# concentrador.net
KiCad netlist of a schematic drawn in Altium Designer
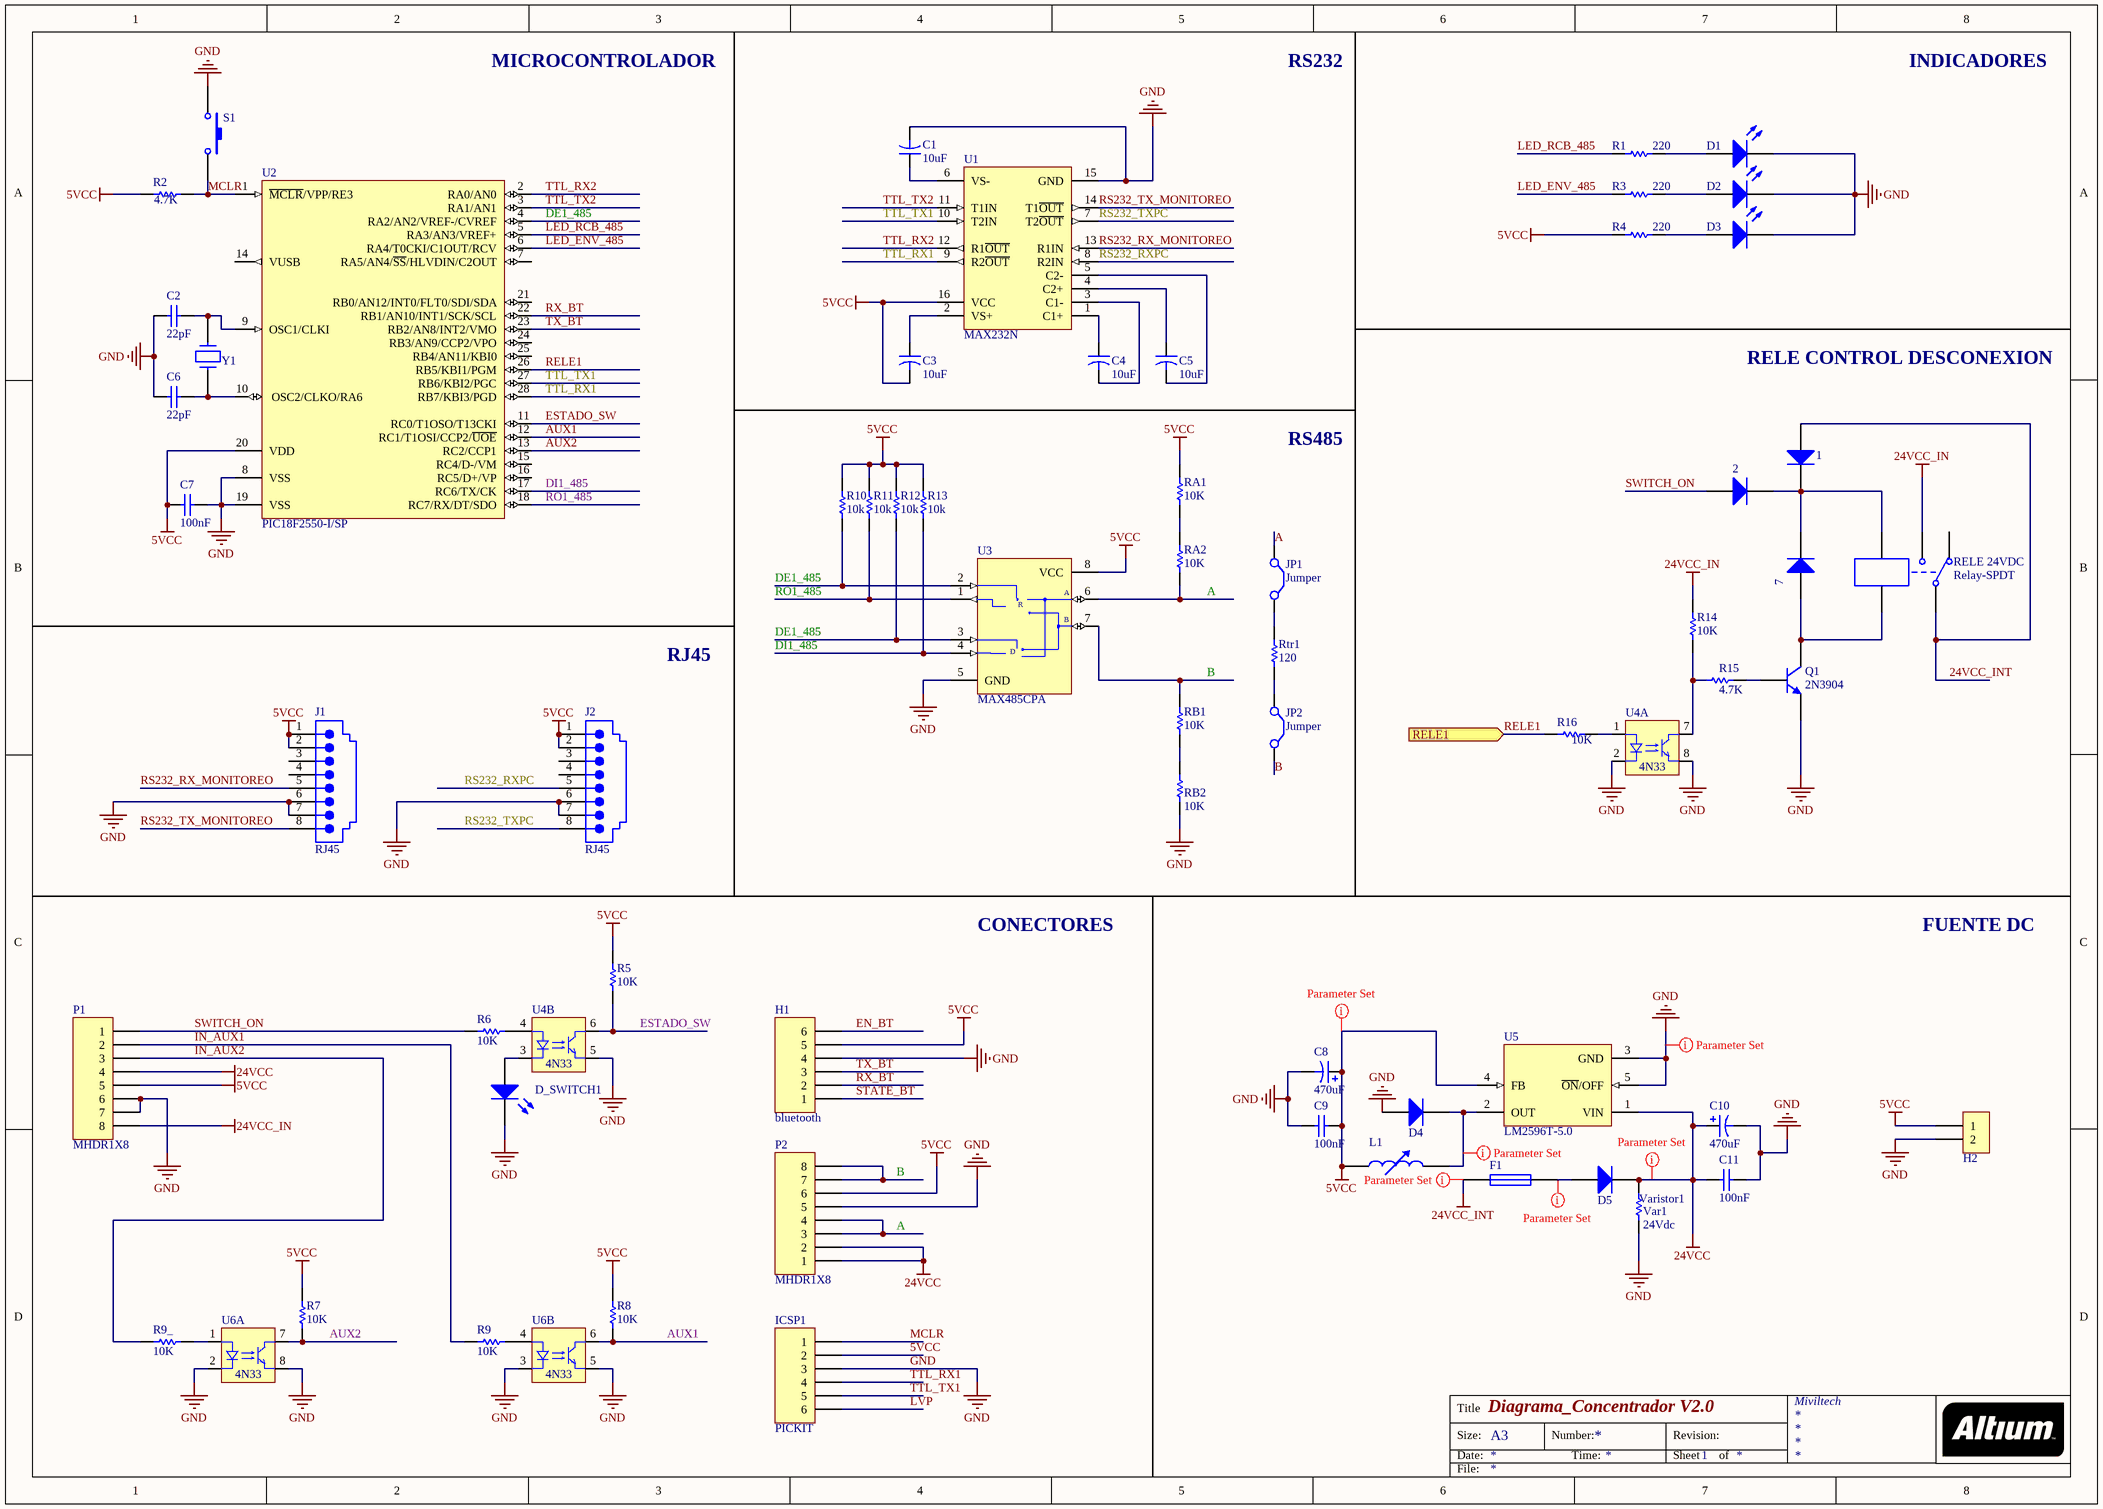
[diagram p0: concentrador.SchDoc]

(export (version "E")
  (design (tool "Eeschema 10.0.6"))
  (components
    (comp (ref "1")
      (value "Diode 1N4001")
      (footprint "DIODE-0.3A")
      (description "1 Amp General Purpose Rectifier")
      (fields (field (name "PUBLISHER") "Altium Limited"))
      (libsource (lib "Miscellaneous Devices") (part "Diode 1N4001"))
    )
    (comp (ref "2")
      (value "Diode 1N4001")
      (footprint "DIODE-0.3A")
      (description "1 Amp General Purpose Rectifier")
      (fields (field (name "PUBLISHER") "Altium Limited"))
      (libsource (lib "Miscellaneous Devices") (part "Diode 1N4001"))
    )
    (comp (ref "7")
      (value "Diode 1N4001")
      (footprint "DIODE-0.3A")
      (description "1 Amp General Purpose Rectifier")
      (fields (field (name "PUBLISHER") "Altium Limited"))
      (libsource (lib "Miscellaneous Devices") (part "Diode 1N4001"))
    )
    (comp (ref "C1")
      (value "10uF")
      (footprint "C1UF")
      (description "Capacitor")
      (fields (field (name "Comment") "Cap2") (field (name "PUBLISHER") "Altium Limited"))
      (libsource (lib "Miscellaneous Devices") (part "Cap2"))
    )
    (comp (ref "C2")
      (value "22pF")
      (footprint "VP31-2.5")
      (description "Dipped Radial Multilayer Ceramic Capacitor COG (NPO): 22pF, 100V")
      (fields (field (name "Comment") "VP31BA220JB") (field (name "PUBLISHER") "Altium Limited"))
      (libsource (lib "Vishay Vitramon Ceramic Dipped Capacitor") (part "VP31BA220JB"))
    )
    (comp (ref "C3")
      (value "10uF")
      (footprint "C1UF")
      (description "Capacitor")
      (fields (field (name "Comment") "Cap2") (field (name "PUBLISHER") "Altium Limited"))
      (libsource (lib "Miscellaneous Devices") (part "Cap2"))
    )
    (comp (ref "C4")
      (value "10uF")
      (footprint "C1UF")
      (description "Capacitor")
      (fields (field (name "Comment") "Cap2") (field (name "PUBLISHER") "Altium Limited"))
      (libsource (lib "Miscellaneous Devices") (part "Cap2"))
    )
    (comp (ref "C5")
      (value "10uF")
      (footprint "C1UF")
      (description "Capacitor")
      (fields (field (name "Comment") "Cap2") (field (name "PUBLISHER") "Altium Limited"))
      (libsource (lib "Miscellaneous Devices") (part "Cap2"))
    )
    (comp (ref "C6")
      (value "22pF")
      (footprint "VP31-2.5")
      (description "Dipped Radial Multilayer Ceramic Capacitor COG (NPO): 22pF, 100V")
      (fields (field (name "Comment") "VP31BA220JB") (field (name "PUBLISHER") "Altium Limited"))
      (libsource (lib "Vishay Vitramon Ceramic Dipped Capacitor") (part "VP31BA220JB"))
    )
    (comp (ref "C7")
      (value "100nF")
      (footprint "VP44-2.5")
      (description "Dipped Radial Multilayer Ceramic Capacitor X7R: 220nF, 100V")
      (fields (field (name "Comment") "VP44BY224JB") (field (name "PUBLISHER") "Altium Limited"))
      (libsource (lib "Vishay Vitramon Ceramic Dipped Capacitor") (part "VP44BY224JB"))
    )
    (comp (ref "C8")
      (value "470uF")
      (footprint "C1000UF")
      (description "Polarized Capacitor (Radial)")
      (fields (field (name "Comment") "Cap Pol1") (field (name "PUBLISHER") "Altium Limited"))
      (libsource (lib "Miscellaneous Devices") (part "Cap Pol1"))
    )
    (comp (ref "C9")
      (value "100nF")
      (footprint "VP44-2.5")
      (description "Dipped Radial Multilayer Ceramic Capacitor X7R: 220nF, 100V")
      (fields (field (name "Comment") "VP44BY224JB") (field (name "PUBLISHER") "Altium Limited"))
      (libsource (lib "Vishay Vitramon Ceramic Dipped Capacitor") (part "VP44BY224JB"))
    )
    (comp (ref "C10")
      (value "470uF")
      (footprint "C1000UF")
      (description "Polarized Capacitor (Radial)")
      (fields (field (name "Comment") "Cap Pol1") (field (name "PUBLISHER") "Altium Limited"))
      (libsource (lib "Miscellaneous Devices") (part "Cap Pol1"))
    )
    (comp (ref "C11")
      (value "100nF")
      (footprint "VP44-2.5")
      (description "Dipped Radial Multilayer Ceramic Capacitor X7R: 220nF, 100V")
      (fields (field (name "Comment") "VP44BY224JB") (field (name "PUBLISHER") "Altium Limited"))
      (libsource (lib "Vishay Vitramon Ceramic Dipped Capacitor") (part "VP44BY224JB"))
    )
    (comp (ref "D1")
      (value "LED0")
      (footprint "LED3MM green")
      (description "Typical INFRARED GaAs LED")
      (fields (field (name "PUBLISHER") "Altium Limited"))
      (libsource (lib "Miscellaneous Devices") (part "LED0"))
    )
    (comp (ref "D2")
      (value "LED0")
      (footprint "LED3MM green")
      (description "Typical INFRARED GaAs LED")
      (fields (field (name "PUBLISHER") "Altium Limited"))
      (libsource (lib "Miscellaneous Devices") (part "LED0"))
    )
    (comp (ref "D3")
      (value "LED0")
      (footprint "LED3MM green")
      (description "Typical INFRARED GaAs LED")
      (fields (field (name "PUBLISHER") "Altium Limited"))
      (libsource (lib "Miscellaneous Devices") (part "LED0"))
    )
    (comp (ref "D4")
      (value "Diodo")
      (footprint "1N4000")
      (description "Diodo rectificador")
      (libsource (lib "Diodos") (part "Diodo"))
    )
    (comp (ref "D5")
      (value "Diodo")
      (footprint "1N4000")
      (description "Diodo rectificador")
      (libsource (lib "Diodos") (part "Diodo"))
    )
    (comp (ref "D_SWITCH1")
      (value "LED0")
      (footprint "LED3MM green")
      (description "Typical INFRARED GaAs LED")
      (fields (field (name "PUBLISHER") "Altium Limited"))
      (libsource (lib "Miscellaneous Devices") (part "LED0"))
    )
    (comp (ref "F1")
      (value "Fuse")
      (footprint "PORTA_FUSE")
      (fields (field (name "PUBLISHER") "Altium Limited"))
      (libsource (lib "Miscellaneous Devices") (part "Fuse 1"))
    )
    (comp (ref "H1")
      (value "bluetooth")
      (footprint "Header 1X6")
      (description "Header, 6-Pin")
      (fields (field (name "PUBLISHER") "Altium Limited"))
      (libsource (lib "Conectores") (part "Header 6"))
    )
    (comp (ref "H2")
      (value "Header")
      (footprint "Header 1X2")
      (description "Header 2 pin")
      (libsource (lib "Conectores") (part "Header 2"))
    )
    (comp (ref "ICSP1")
      (value "PICKIT")
      (footprint "HDR1X6")
      (description "Header, 6-Pin")
      (fields (field (name "PUBLISHER") "Altium Limited"))
      (libsource (lib "CONTROL BARRAS DE CONTEO") (part "Header 6"))
    )
    (comp (ref "J1")
      (value "RJ45")
      (footprint "15-43-6233")
      (description "Right Angle, Standard Profile, RJ45-Keyed, Flange Mount PCB Jack")
      (fields (field (name "PUBLISHER") "Altium Limited"))
      (libsource (lib "Molex Modular Jack Right Angle") (part "15-43-6233"))
    )
    (comp (ref "J2")
      (value "RJ45")
      (footprint "15-43-6233")
      (description "Right Angle, Standard Profile, RJ45-Keyed, Flange Mount PCB Jack")
      (fields (field (name "PUBLISHER") "Altium Limited"))
      (libsource (lib "Molex Modular Jack Right Angle") (part "15-43-6233"))
    )
    (comp (ref "JP1")
      (value "Jumper")
      (footprint "RAD-0.2")
      (description "Jumper Wire")
      (fields (field (name "PUBLISHER") "Altium Limited"))
      (libsource (lib "Miscellaneous Devices") (part "Jumper"))
    )
    (comp (ref "JP2")
      (value "Jumper")
      (footprint "RAD-0.2")
      (description "Jumper Wire")
      (fields (field (name "PUBLISHER") "Altium Limited"))
      (libsource (lib "Miscellaneous Devices") (part "Jumper"))
    )
    (comp (ref "L1")
      (value "Inductor Adj")
      (footprint "Inductor_redondo")
      (description "Adjustable Inductor")
      (fields (field (name "PUBLISHER") "Altium Limited"))
      (libsource (lib "Miscellaneous Devices") (part "Inductor Adj"))
    )
    (comp (ref "P1")
      (value "MHDR1X8")
      (footprint "8PEQ_TAIYUE_OK")
      (description "Header, 8-Pin")
      (fields (field (name "PUBLISHER") "Altium Limited"))
      (libsource (lib "Miscellaneous Connectors") (part "MHDR1X8"))
    )
    (comp (ref "P2")
      (value "MHDR1X8")
      (footprint "8PEQ_TAIYUE_OK")
      (description "Header, 8-Pin")
      (fields (field (name "PUBLISHER") "Altium Limited"))
      (libsource (lib "") (part "MHDR1X8_1"))
    )
    (comp (ref "Q1")
      (value "2N3904")
      (footprint "2N3904_OK")
      (description "NPN General Purpose Amplifier")
      (fields (field (name "PUBLISHER") "Altium Limited"))
      (libsource (lib "Miscellaneous Devices") (part "2N3904"))
    )
    (comp (ref "R1")
      (value "220")
      (footprint "AXIAL-0.3")
      (description "Resistor")
      (fields (field (name "Comment") "Res1") (field (name "PUBLISHER") "Altium Limited"))
      (libsource (lib "Miscellaneous Devices") (part "Res1"))
    )
    (comp (ref "R2")
      (value "4.7K")
      (footprint "AXIAL-0.3")
      (description "Resistor")
      (fields (field (name "Comment") "Res1") (field (name "PUBLISHER") "Altium Limited"))
      (libsource (lib "Miscellaneous Devices") (part "Res1"))
    )
    (comp (ref "R3")
      (value "220")
      (footprint "AXIAL-0.3")
      (description "Resistor")
      (fields (field (name "Comment") "Res1") (field (name "PUBLISHER") "Altium Limited"))
      (libsource (lib "Miscellaneous Devices") (part "Res1"))
    )
    (comp (ref "R4")
      (value "220")
      (footprint "AXIAL-0.3")
      (description "Resistor")
      (fields (field (name "Comment") "Res1") (field (name "PUBLISHER") "Altium Limited"))
      (libsource (lib "Miscellaneous Devices") (part "Res1"))
    )
    (comp (ref "R5")
      (value "10K")
      (footprint "AXIAL-0.3")
      (description "Resistor")
      (fields (field (name "Comment") "Res1") (field (name "PUBLISHER") "Altium Limited"))
      (libsource (lib "Miscellaneous Devices") (part "Res1"))
    )
    (comp (ref "R6")
      (value "10K")
      (footprint "AXIAL-0.3")
      (description "Resistor")
      (fields (field (name "Comment") "Res1") (field (name "PUBLISHER") "Altium Limited"))
      (libsource (lib "Miscellaneous Devices") (part "Res1"))
    )
    (comp (ref "R7")
      (value "10K")
      (footprint "AXIAL-0.3")
      (description "Resistor")
      (fields (field (name "Comment") "Res1") (field (name "PUBLISHER") "Altium Limited"))
      (libsource (lib "Miscellaneous Devices") (part "Res1"))
    )
    (comp (ref "R8")
      (value "10K")
      (footprint "AXIAL-0.3")
      (description "Resistor")
      (fields (field (name "Comment") "Res1") (field (name "PUBLISHER") "Altium Limited"))
      (libsource (lib "Miscellaneous Devices") (part "Res1"))
    )
    (comp (ref "R9")
      (value "10K")
      (footprint "AXIAL-0.3")
      (description "Resistor")
      (fields (field (name "Comment") "Res1") (field (name "PUBLISHER") "Altium Limited"))
      (libsource (lib "Miscellaneous Devices") (part "Res1"))
    )
    (comp (ref "R9_")
      (value "10K")
      (footprint "AXIAL-0.3")
      (description "Resistor")
      (fields (field (name "Comment") "Res1") (field (name "PUBLISHER") "Altium Limited"))
      (libsource (lib "Miscellaneous Devices") (part "Res1"))
    )
    (comp (ref "R10")
      (value "10k")
      (footprint "AXIAL-0.3")
      (description "Resistor")
      (fields (field (name "Comment") "Res1") (field (name "PUBLISHER") "Altium Limited"))
      (libsource (lib "Miscellaneous Devices") (part "Res1"))
    )
    (comp (ref "R11")
      (value "10k")
      (footprint "AXIAL-0.3")
      (description "Resistor")
      (fields (field (name "Comment") "Res1") (field (name "PUBLISHER") "Altium Limited"))
      (libsource (lib "Miscellaneous Devices") (part "Res1"))
    )
    (comp (ref "R12")
      (value "10k")
      (footprint "AXIAL-0.3")
      (description "Resistor")
      (fields (field (name "Comment") "Res1") (field (name "PUBLISHER") "Altium Limited"))
      (libsource (lib "Miscellaneous Devices") (part "Res1"))
    )
    (comp (ref "R13")
      (value "10k")
      (footprint "AXIAL-0.3")
      (description "Resistor")
      (fields (field (name "Comment") "Res1") (field (name "PUBLISHER") "Altium Limited"))
      (libsource (lib "Miscellaneous Devices") (part "Res1"))
    )
    (comp (ref "R14")
      (value "10K")
      (footprint "AXIAL-0.3")
      (description "Resistor")
      (fields (field (name "Comment") "Res1") (field (name "PUBLISHER") "Altium Limited"))
      (libsource (lib "Miscellaneous Devices") (part "Res1"))
    )
    (comp (ref "R15")
      (value "4.7K")
      (footprint "AXIAL-0.3")
      (description "Resistor")
      (fields (field (name "Comment") "Res1") (field (name "PUBLISHER") "Altium Limited"))
      (libsource (lib "Miscellaneous Devices") (part "Res1"))
    )
    (comp (ref "R16")
      (value "10K")
      (footprint "AXIAL-0.3")
      (description "Resistor")
      (fields (field (name "Comment") "Res1") (field (name "PUBLISHER") "Altium Limited"))
      (libsource (lib "Miscellaneous Devices") (part "Res1"))
    )
    (comp (ref "RA1")
      (value "10K")
      (footprint "AXIAL-0.3")
      (description "Resistor")
      (fields (field (name "Comment") "Res1") (field (name "PUBLISHER") "Altium Limited"))
      (libsource (lib "Miscellaneous Devices") (part "Res1"))
    )
    (comp (ref "RA2")
      (value "10K")
      (footprint "AXIAL-0.3")
      (description "Resistor")
      (fields (field (name "Comment") "Res1") (field (name "PUBLISHER") "Altium Limited"))
      (libsource (lib "Miscellaneous Devices") (part "Res1"))
    )
    (comp (ref "RB1")
      (value "10K")
      (footprint "AXIAL-0.3")
      (description "Resistor")
      (fields (field (name "Comment") "Res1") (field (name "PUBLISHER") "Altium Limited"))
      (libsource (lib "Miscellaneous Devices") (part "Res1"))
    )
    (comp (ref "RB2")
      (value "10K")
      (footprint "AXIAL-0.3")
      (description "Resistor")
      (fields (field (name "Comment") "Res1") (field (name "PUBLISHER") "Altium Limited"))
      (libsource (lib "Miscellaneous Devices") (part "Res1"))
    )
    (comp (ref "RELE 24VDC")
      (value "Relay-SPDT")
      (footprint "MODULE5B")
      (description "Single-Pole Dual-Throw Relay")
      (fields (field (name "PUBLISHER") "Altium Limited"))
      (libsource (lib "Miscellaneous Devices") (part "Relay-SPDT"))
    )
    (comp (ref "Rtr1")
      (value "120")
      (footprint "AXIAL-0.3")
      (description "Resistor")
      (fields (field (name "Comment") "Res1") (field (name "PUBLISHER") "Altium Limited"))
      (libsource (lib "Miscellaneous Devices") (part "Res1"))
    )
    (comp (ref "S1")
      (value "Push Button")
      (footprint "PULSA4")
      (description "Switch")
      (fields (field (name "PUBLISHER") "Altium Limited"))
      (libsource (lib "Botones") (part "Push Button"))
    )
    (comp (ref "U1")
      (value "MAX232N")
      (footprint "N016")
      (description "Dual EIA-232 Driver/Receiver")
      (fields (field (name "PUBLISHER") "Altium Limited"))
      (libsource (lib "TI Interface Line Transceiver") (part "MAX232N"))
    )
    (comp (ref "U2")
      (value "PIC18F2550-I/SP")
      (footprint "SPDIP300-SP28")
      (fields (field (name "PUBLISHER") "Altium Limited"))
      (libsource (lib "Microchip Microcontroller 8-Bit PIC18") (part "PIC18F2550-I/SP"))
    )
    (comp (ref "U3")
      (value "MAX485CPA")
      (footprint "PA8")
      (description "Low-Power, Slew-Rate-Limited RS-485/RS-422 Transceiver")
      (fields (field (name "PUBLISHER") "Altium Limited"))
      (libsource (lib "Maxim Communication Transceiver") (part "MAX485CPA"))
    )
    (comp (ref "U4")
      (value "4N33")
      (footprint "4n35_4n33_6pines")
      (description "Optocoupler, Phototransistor Output, Dual Channel, TTL Compatible, Pb-free")
      (fields (field (name "PUBLISHER") "Altium Limited"))
      (libsource (lib "Vishay Optoelectronic Optocoupler") (part "ILD74"))
    )
    (comp (ref "U5")
      (value "LM2596T-5.0")
      (footprint "FP_LM2596_D_PCB")
      (description "SIMPLE SWITCHER Power Converter 150 KHz 3A Step-Down Voltage Regulator")
      (fields
        (field (name "MANUFACTURER") "National Semiconductor")
        (field (name "DIGIKEYPARTNUMBER") "LM2596T-5.0-ND")
        (field (name "PUBLISHER") "Altium Limited")
      )
      (libsource (lib "NSC Switcher") (part "LM2596T-5.0"))
    )
    (comp (ref "U6")
      (value "4N33")
      (footprint "4n35_4n33_6pines")
      (description "Optocoupler, Phototransistor Output, Dual Channel, TTL Compatible, Pb-free")
      (fields (field (name "PUBLISHER") "Altium Limited"))
      (libsource (lib "Vishay Optoelectronic Optocoupler") (part "ILD74"))
    )
    (comp (ref "Varistor1")
      (value "Var1")
      (footprint "AXIAL-0.3")
      (description "Resistor")
      (fields (field (name "ALTIUM_VALUE") "24Vdc") (field (name "PUBLISHER") "Altium Limited"))
      (libsource (lib "Miscellaneous Devices") (part "Res1"))
    )
    (comp (ref "Y1")
      (value "XTAL")
      (footprint "Cristal mini")
      (description "Cristal de cuarzo")
      (libsource (lib "Cristales de cuarzo") (part "Cristal de cuarzo"))
    )
  )
  (nets
    (net (code "1") (name "/A") (class "Default")
      (node (ref "JP1") (pin "1") (pinfunction "C1_1") (pintype "passive"))
      (node (ref "P2") (pin "3") (pinfunction "3_3") (pintype "passive"))
      (node (ref "P2") (pin "4") (pinfunction "4_4") (pintype "passive"))
      (node (ref "RA2") (pin "1") (pinfunction "1_1") (pintype "passive"))
      (node (ref "U3") (pin "6") (pinfunction "A_6") (pintype "bidirectional"))
    )
    (net (code "2") (name "/AUX1") (class "Default")
      (node (ref "R8") (pin "2") (pinfunction "2_2") (pintype "passive"))
      (node (ref "U2") (pin "12") (pinfunction "RC1/T1OSI/CCP2/~{UOE}_12") (pintype "bidirectional"))
      (node (ref "U6") (pin "6") (pinfunction "C_6") (pintype "passive"))
    )
    (net (code "3") (name "/AUX2") (class "Default")
      (node (ref "R7") (pin "2") (pinfunction "2_2") (pintype "passive"))
      (node (ref "U2") (pin "13") (pinfunction "RC2/CCP1_13") (pintype "bidirectional"))
      (node (ref "U6") (pin "7") (pinfunction "C_7") (pintype "passive"))
    )
    (net (code "4") (name "/B") (class "Default")
      (node (ref "JP2") (pin "2") (pinfunction "C2_2") (pintype "passive"))
      (node (ref "P2") (pin "7") (pinfunction "7_7") (pintype "passive"))
      (node (ref "P2") (pin "8") (pinfunction "8_8") (pintype "passive"))
      (node (ref "RB1") (pin "1") (pinfunction "1_1") (pintype "passive"))
      (node (ref "U3") (pin "7") (pinfunction "B_7") (pintype "bidirectional"))
    )
    (net (code "5") (name "/DE1_485") (class "Default")
      (node (ref "R10") (pin "1") (pinfunction "1_1") (pintype "passive"))
      (node (ref "R12") (pin "1") (pinfunction "1_1") (pintype "passive"))
      (node (ref "U2") (pin "4") (pinfunction "RA2/AN2/VREF-/CVREF_4") (pintype "bidirectional"))
      (node (ref "U3") (pin "2") (pinfunction "~{RE}_2") (pintype "input"))
      (node (ref "U3") (pin "3") (pinfunction "DE_3") (pintype "input"))
    )
    (net (code "6") (name "/DI1_485") (class "Default")
      (node (ref "R13") (pin "1") (pinfunction "1_1") (pintype "passive"))
      (node (ref "U2") (pin "17") (pinfunction "RC6/TX/CK_17") (pintype "bidirectional"))
      (node (ref "U3") (pin "4") (pinfunction "DI_4") (pintype "input"))
    )
    (net (code "7") (name "/EN_BT") (class "Default")
      (node (ref "H1") (pin "6") (pinfunction "6_6") (pintype "passive"))
    )
    (net (code "8") (name "/ESTADO_SW") (class "Default")
      (node (ref "R5") (pin "2") (pinfunction "2_2") (pintype "passive"))
      (node (ref "U2") (pin "11") (pinfunction "RC0/T1OSO/T13CKI_11") (pintype "bidirectional"))
      (node (ref "U4") (pin "6") (pinfunction "C_6") (pintype "passive"))
    )
    (net (code "9") (name "/IN_AUX1") (class "Default")
      (node (ref "P1") (pin "2") (pinfunction "2_2") (pintype "passive"))
      (node (ref "R9") (pin "2") (pinfunction "2_2") (pintype "passive"))
    )
    (net (code "10") (name "/IN_AUX2") (class "Default")
      (node (ref "P1") (pin "3") (pinfunction "3_3") (pintype "passive"))
      (node (ref "R9_") (pin "2") (pinfunction "2_2") (pintype "passive"))
    )
    (net (code "11") (name "/LED_ENV_485") (class "Default")
      (node (ref "R3") (pin "1") (pinfunction "1_1") (pintype "passive"))
      (node (ref "U2") (pin "6") (pinfunction "RA4/T0CKI/C1OUT/RCV_6") (pintype "bidirectional"))
    )
    (net (code "12") (name "/LED_RCB_485") (class "Default")
      (node (ref "R1") (pin "1") (pinfunction "1_1") (pintype "passive"))
      (node (ref "U2") (pin "5") (pinfunction "RA3/AN3/VREF+_5") (pintype "bidirectional"))
    )
    (net (code "13") (name "/LVP") (class "Default")
      (node (ref "ICSP1") (pin "6") (pinfunction "6_6") (pintype "passive"))
    )
    (net (code "14") (name "/MCLR") (class "Default")
      (node (ref "ICSP1") (pin "1") (pinfunction "1_1") (pintype "passive"))
      (node (ref "R2") (pin "2") (pinfunction "2_2") (pintype "passive"))
      (node (ref "S1") (pin "2") (pinfunction "2_2") (pintype "passive"))
      (node (ref "U2") (pin "1") (pinfunction "~{MCLR}/VPP/RE3_1") (pintype "input"))
    )
    (net (code "15") (name "/RELE1") (class "Default")
      (node (ref "R16") (pin "2") (pinfunction "2_2") (pintype "passive"))
      (node (ref "U2") (pin "26") (pinfunction "RB5/KBI1/PGM_26") (pintype "bidirectional"))
    )
    (net (code "16") (name "/RO1_485") (class "Default")
      (node (ref "R11") (pin "1") (pinfunction "1_1") (pintype "passive"))
      (node (ref "U2") (pin "18") (pinfunction "RC7/RX/DT/SDO_18") (pintype "bidirectional"))
      (node (ref "U3") (pin "1") (pinfunction "RO_1") (pintype "output"))
    )
    (net (code "17") (name "/RS232_RXPC") (class "Default")
      (node (ref "J2") (pin "5") (pinfunction "5_5") (pintype "passive"))
      (node (ref "U1") (pin "8") (pinfunction "R2IN_8") (pintype "input"))
    )
    (net (code "18") (name "/RS232_RX_MONITOREO") (class "Default")
      (node (ref "J1") (pin "5") (pinfunction "5_5") (pintype "passive"))
      (node (ref "U1") (pin "13") (pinfunction "R1IN_13") (pintype "input"))
    )
    (net (code "19") (name "/RS232_TXPC") (class "Default")
      (node (ref "J2") (pin "8") (pinfunction "8_8") (pintype "passive"))
      (node (ref "U1") (pin "7") (pinfunction "T2~{OUT}_7") (pintype "output"))
    )
    (net (code "20") (name "/RS232_TX_MONITOREO") (class "Default")
      (node (ref "J1") (pin "8") (pinfunction "8_8") (pintype "passive"))
      (node (ref "U1") (pin "14") (pinfunction "T1~{OUT}_14") (pintype "output"))
    )
    (net (code "21") (name "/RX_BT") (class "Default")
      (node (ref "H1") (pin "2") (pinfunction "2_2") (pintype "passive"))
      (node (ref "U2") (pin "22") (pinfunction "RB1/AN10/INT1/SCK/SCL_22") (pintype "bidirectional"))
    )
    (net (code "22") (name "/STATE_BT") (class "Default")
      (node (ref "H1") (pin "1") (pinfunction "1_1") (pintype "passive"))
    )
    (net (code "23") (name "/SWITCH_ON") (class "Default")
      (node (ref "2") (pin "1") (pinfunction "A_1") (pintype "passive"))
      (node (ref "P1") (pin "1") (pinfunction "1_1") (pintype "passive"))
      (node (ref "R6") (pin "2") (pinfunction "2_2") (pintype "passive"))
    )
    (net (code "24") (name "/TTL_RX1") (class "Default")
      (node (ref "ICSP1") (pin "4") (pinfunction "4_4") (pintype "passive"))
      (node (ref "U1") (pin "9") (pinfunction "R2~{OUT}_9") (pintype "output"))
      (node (ref "U2") (pin "28") (pinfunction "RB7/KBI3/PGD_28") (pintype "bidirectional"))
    )
    (net (code "25") (name "/TTL_RX2") (class "Default")
      (node (ref "U1") (pin "12") (pinfunction "R1~{OUT}_12") (pintype "output"))
      (node (ref "U2") (pin "2") (pinfunction "RA0/AN0_2") (pintype "bidirectional"))
    )
    (net (code "26") (name "/TTL_TX1") (class "Default")
      (node (ref "ICSP1") (pin "5") (pinfunction "5_5") (pintype "passive"))
      (node (ref "U1") (pin "10") (pinfunction "T2IN_10") (pintype "input"))
      (node (ref "U2") (pin "27") (pinfunction "RB6/KBI2/PGC_27") (pintype "bidirectional"))
    )
    (net (code "27") (name "/TTL_TX2") (class "Default")
      (node (ref "U1") (pin "11") (pinfunction "T1IN_11") (pintype "input"))
      (node (ref "U2") (pin "3") (pinfunction "RA1/AN1_3") (pintype "bidirectional"))
    )
    (net (code "28") (name "/TX_BT") (class "Default")
      (node (ref "H1") (pin "3") (pinfunction "3_3") (pintype "passive"))
      (node (ref "U2") (pin "23") (pinfunction "RB2/AN8/INT2/VMO_23") (pintype "bidirectional"))
    )
    (net (code "29") (name "5VCC") (class "Default")
      (node (ref "C3") (pin "2") (pinfunction "2_2") (pintype "passive"))
      (node (ref "C7") (pin "1") (pinfunction "1_1") (pintype "passive"))
      (node (ref "C8") (pin "1") (pinfunction "1_1") (pintype "passive"))
      (node (ref "C9") (pin "2") (pinfunction "2_2") (pintype "passive"))
      (node (ref "H1") (pin "5") (pinfunction "5_5") (pintype "passive"))
      (node (ref "H2") (pin "1") (pinfunction "1_1") (pintype "passive"))
      (node (ref "ICSP1") (pin "2") (pinfunction "2_2") (pintype "passive"))
      (node (ref "J1") (pin "1") (pinfunction "1_1") (pintype "passive"))
      (node (ref "J1") (pin "2") (pinfunction "2_2") (pintype "passive"))
      (node (ref "J2") (pin "1") (pinfunction "1_1") (pintype "passive"))
      (node (ref "J2") (pin "2") (pinfunction "2_2") (pintype "passive"))
      (node (ref "L1") (pin "1") (pinfunction "1_1") (pintype "passive"))
      (node (ref "P1") (pin "5") (pinfunction "5_5") (pintype "passive"))
      (node (ref "P2") (pin "6") (pinfunction "6_6") (pintype "passive"))
      (node (ref "R10") (pin "2") (pinfunction "2_2") (pintype "passive"))
      (node (ref "R11") (pin "2") (pinfunction "2_2") (pintype "passive"))
      (node (ref "R12") (pin "2") (pinfunction "2_2") (pintype "passive"))
      (node (ref "R13") (pin "2") (pinfunction "2_2") (pintype "passive"))
      (node (ref "R2") (pin "1") (pinfunction "1_1") (pintype "passive"))
      (node (ref "R4") (pin "1") (pinfunction "1_1") (pintype "passive"))
      (node (ref "R5") (pin "1") (pinfunction "1_1") (pintype "passive"))
      (node (ref "R7") (pin "1") (pinfunction "1_1") (pintype "passive"))
      (node (ref "R8") (pin "1") (pinfunction "1_1") (pintype "passive"))
      (node (ref "RA1") (pin "1") (pinfunction "1_1") (pintype "passive"))
      (node (ref "U1") (pin "16") (pinfunction "VCC_16") (pintype "power_in"))
      (node (ref "U2") (pin "20") (pinfunction "VDD_20") (pintype "power_in"))
      (node (ref "U3") (pin "8") (pinfunction "VCC_8") (pintype "power_in"))
      (node (ref "U5") (pin "4") (pinfunction "FB_4") (pintype "input"))
    )
    (net (code "30") (name "24VCC") (class "Default")
      (node (ref "C10") (pin "1") (pinfunction "1_1") (pintype "passive"))
      (node (ref "C11") (pin "1") (pinfunction "1_1") (pintype "passive"))
      (node (ref "D5") (pin "2") (pinfunction "K_2") (pintype "passive"))
      (node (ref "P1") (pin "4") (pinfunction "4_4") (pintype "passive"))
      (node (ref "P2") (pin "1") (pinfunction "1_1") (pintype "passive"))
      (node (ref "P2") (pin "2") (pinfunction "2_2") (pintype "passive"))
      (node (ref "U5") (pin "1") (pinfunction "VIN_1") (pintype "power_in"))
      (node (ref "Varistor1") (pin "2") (pinfunction "2_2") (pintype "passive"))
    )
    (net (code "31") (name "24VCC_IN") (class "Default")
      (node (ref "P1") (pin "8") (pinfunction "8_8") (pintype "passive"))
      (node (ref "R14") (pin "1") (pinfunction "1_1") (pintype "passive"))
      (node (ref "RELE 24VDC") (pin "3") (pinfunction "3_3") (pintype "passive"))
    )
    (net (code "32") (name "24VCC_INT") (class "Default")
      (node (ref "1") (pin "1") (pinfunction "A_1") (pintype "passive"))
      (node (ref "F1") (pin "2") (pinfunction "2_2") (pintype "passive"))
      (node (ref "RELE 24VDC") (pin "1") (pinfunction "1_1") (pintype "passive"))
    )
    (net (code "33") (name "GND") (class "Default")
      (node (ref "C1") (pin "2") (pinfunction "2_2") (pintype "passive"))
      (node (ref "C10") (pin "2") (pinfunction "2_2") (pintype "passive"))
      (node (ref "C11") (pin "2") (pinfunction "2_2") (pintype "passive"))
      (node (ref "C2") (pin "2") (pinfunction "2_2") (pintype "passive"))
      (node (ref "C6") (pin "2") (pinfunction "2_2") (pintype "passive"))
      (node (ref "C7") (pin "2") (pinfunction "2_2") (pintype "passive"))
      (node (ref "C8") (pin "2") (pinfunction "2_2") (pintype "passive"))
      (node (ref "C9") (pin "1") (pinfunction "1_1") (pintype "passive"))
      (node (ref "D1") (pin "2") (pinfunction "K_2") (pintype "passive"))
      (node (ref "D2") (pin "2") (pinfunction "K_2") (pintype "passive"))
      (node (ref "D3") (pin "2") (pinfunction "K_2") (pintype "passive"))
      (node (ref "D4") (pin "1") (pinfunction "A_1") (pintype "passive"))
      (node (ref "D_SWITCH1") (pin "2") (pinfunction "K_2") (pintype "passive"))
      (node (ref "H1") (pin "4") (pinfunction "4_4") (pintype "passive"))
      (node (ref "H2") (pin "2") (pinfunction "2_2") (pintype "passive"))
      (node (ref "ICSP1") (pin "3") (pinfunction "3_3") (pintype "passive"))
      (node (ref "J1") (pin "6") (pinfunction "6_6") (pintype "passive"))
      (node (ref "J1") (pin "7") (pinfunction "7_7") (pintype "passive"))
      (node (ref "J2") (pin "6") (pinfunction "6_6") (pintype "passive"))
      (node (ref "J2") (pin "7") (pinfunction "7_7") (pintype "passive"))
      (node (ref "P1") (pin "6") (pinfunction "6_6") (pintype "passive"))
      (node (ref "P1") (pin "7") (pinfunction "7_7") (pintype "passive"))
      (node (ref "P2") (pin "5") (pinfunction "5_5") (pintype "passive"))
      (node (ref "Q1") (pin "1") (pinfunction "E_1") (pintype "passive"))
      (node (ref "RB2") (pin "1") (pinfunction "1_1") (pintype "passive"))
      (node (ref "S1") (pin "1") (pinfunction "1_1") (pintype "passive"))
      (node (ref "U1") (pin "15") (pinfunction "GND_15") (pintype "power_in"))
      (node (ref "U2") (pin "19") (pinfunction "VSS_19") (pintype "power_in"))
      (node (ref "U2") (pin "8") (pinfunction "VSS_8") (pintype "power_in"))
      (node (ref "U3") (pin "5") (pinfunction "GND_5") (pintype "power_in"))
      (node (ref "U4") (pin "2") (pinfunction "K_2") (pintype "passive"))
      (node (ref "U4") (pin "5") (pinfunction "E_5") (pintype "passive"))
      (node (ref "U4") (pin "8") (pinfunction "E_8") (pintype "passive"))
      (node (ref "U5") (pin "3") (pinfunction "GND_3") (pintype "power_in"))
      (node (ref "U5") (pin "5") (pinfunction "~{ON}/OFF_5") (pintype "input"))
      (node (ref "U6") (pin "2") (pinfunction "K_2") (pintype "passive"))
      (node (ref "U6") (pin "3") (pinfunction "K_3") (pintype "passive"))
      (node (ref "U6") (pin "5") (pinfunction "E_5") (pintype "passive"))
      (node (ref "U6") (pin "8") (pinfunction "E_8") (pintype "passive"))
      (node (ref "Varistor1") (pin "1") (pinfunction "1_1") (pintype "passive"))
    )
    (net (code "34") (name "Net-(1-K)") (class "Default")
      (node (ref "1") (pin "2") (pinfunction "K_2") (pintype "passive"))
      (node (ref "2") (pin "2") (pinfunction "K_2") (pintype "passive"))
      (node (ref "7") (pin "2") (pinfunction "K_2") (pintype "passive"))
      (node (ref "RELE 24VDC") (pin "5") (pinfunction "5_5") (pintype "passive"))
    )
    (net (code "35") (name "Net-(7-A)") (class "Default")
      (node (ref "7") (pin "1") (pinfunction "A_1") (pintype "passive"))
      (node (ref "Q1") (pin "3") (pinfunction "C_3") (pintype "passive"))
      (node (ref "RELE 24VDC") (pin "4") (pinfunction "4_4") (pintype "passive"))
    )
    (net (code "36") (name "Net-(D1-A)") (class "Default")
      (node (ref "D1") (pin "1") (pinfunction "A_1") (pintype "passive"))
      (node (ref "R1") (pin "2") (pinfunction "2_2") (pintype "passive"))
    )
    (net (code "37") (name "Net-(D2-A)") (class "Default")
      (node (ref "D2") (pin "1") (pinfunction "A_1") (pintype "passive"))
      (node (ref "R3") (pin "2") (pinfunction "2_2") (pintype "passive"))
    )
    (net (code "38") (name "Net-(D3-A)") (class "Default")
      (node (ref "D3") (pin "1") (pinfunction "A_1") (pintype "passive"))
      (node (ref "R4") (pin "2") (pinfunction "2_2") (pintype "passive"))
    )
    (net (code "39") (name "Net-(D4-K)") (class "Default")
      (node (ref "D4") (pin "2") (pinfunction "K_2") (pintype "passive"))
      (node (ref "L1") (pin "2") (pinfunction "2_2") (pintype "passive"))
      (node (ref "U5") (pin "2") (pinfunction "OUT_2") (pintype "power_in"))
    )
    (net (code "40") (name "Net-(D5-A)") (class "Default")
      (node (ref "D5") (pin "1") (pinfunction "A_1") (pintype "passive"))
      (node (ref "F1") (pin "1") (pinfunction "1_1") (pintype "passive"))
    )
    (net (code "41") (name "Net-(D_SWITCH1-A)") (class "Default")
      (node (ref "D_SWITCH1") (pin "1") (pinfunction "A_1") (pintype "passive"))
      (node (ref "U4") (pin "3") (pinfunction "K_3") (pintype "passive"))
    )
    (net (code "42") (name "Net-(JP1-C2)") (class "Default")
      (node (ref "JP1") (pin "2") (pinfunction "C2_2") (pintype "passive"))
      (node (ref "Rtr1") (pin "2") (pinfunction "2_2") (pintype "passive"))
    )
    (net (code "43") (name "Net-(JP2-C1)") (class "Default")
      (node (ref "JP2") (pin "1") (pinfunction "C1_1") (pintype "passive"))
      (node (ref "Rtr1") (pin "1") (pinfunction "1_1") (pintype "passive"))
    )
    (net (code "44") (name "Net-(Q1-B)") (class "Default")
      (node (ref "Q1") (pin "2") (pinfunction "B_2") (pintype "passive"))
      (node (ref "R15") (pin "2") (pinfunction "2_2") (pintype "passive"))
    )
    (net (code "45") (name "Net-(RA1-Pad2)") (class "Default")
      (node (ref "RA1") (pin "2") (pinfunction "2_2") (pintype "passive"))
      (node (ref "RA2") (pin "2") (pinfunction "2_2") (pintype "passive"))
    )
    (net (code "46") (name "Net-(RB1-Pad2)") (class "Default")
      (node (ref "RB1") (pin "2") (pinfunction "2_2") (pintype "passive"))
      (node (ref "RB2") (pin "2") (pinfunction "2_2") (pintype "passive"))
    )
    (net (code "47") (name "Net-(U1-C1+)") (class "Default")
      (node (ref "C4") (pin "1") (pinfunction "1_1") (pintype "passive"))
      (node (ref "U1") (pin "1") (pinfunction "C1+_1") (pintype "passive"))
    )
    (net (code "48") (name "Net-(U1-C1-)") (class "Default")
      (node (ref "C4") (pin "2") (pinfunction "2_2") (pintype "passive"))
      (node (ref "U1") (pin "3") (pinfunction "C1-_3") (pintype "passive"))
    )
    (net (code "49") (name "Net-(U1-C2+)") (class "Default")
      (node (ref "C5") (pin "1") (pinfunction "1_1") (pintype "passive"))
      (node (ref "U1") (pin "4") (pinfunction "C2+_4") (pintype "passive"))
    )
    (net (code "50") (name "Net-(U1-C2-)") (class "Default")
      (node (ref "C5") (pin "2") (pinfunction "2_2") (pintype "passive"))
      (node (ref "U1") (pin "5") (pinfunction "C2-_5") (pintype "passive"))
    )
    (net (code "51") (name "Net-(U1-VS+)") (class "Default")
      (node (ref "C3") (pin "1") (pinfunction "1_1") (pintype "passive"))
      (node (ref "U1") (pin "2") (pinfunction "VS+_2") (pintype "power_in"))
    )
    (net (code "52") (name "Net-(U1-VS-)") (class "Default")
      (node (ref "C1") (pin "1") (pinfunction "1_1") (pintype "passive"))
      (node (ref "U1") (pin "6") (pinfunction "VS-_6") (pintype "power_in"))
    )
    (net (code "53") (name "Net-(U2-OSC1{slash}CLKI)") (class "Default")
      (node (ref "C2") (pin "1") (pinfunction "1_1") (pintype "passive"))
      (node (ref "U2") (pin "9") (pinfunction "OSC1/CLKI_9") (pintype "input"))
      (node (ref "Y1") (pin "2") (pinfunction "2_2") (pintype "passive"))
    )
    (net (code "54") (name "Net-(U2-OSC2{slash}CLKO{slash}RA6)") (class "Default")
      (node (ref "C6") (pin "1") (pinfunction "1_1") (pintype "passive"))
      (node (ref "U2") (pin "10") (pinfunction "OSC2/CLKO/RA6_10") (pintype "bidirectional"))
      (node (ref "Y1") (pin "1") (pinfunction "1_1") (pintype "passive"))
    )
    (net (code "55") (name "Net-(U4A-A)") (class "Default")
      (node (ref "R16") (pin "1") (pinfunction "1_1") (pintype "passive"))
      (node (ref "U4") (pin "1") (pinfunction "A_1") (pintype "passive"))
    )
    (net (code "56") (name "Net-(U4A-C)") (class "Default")
      (node (ref "R14") (pin "2") (pinfunction "2_2") (pintype "passive"))
      (node (ref "R15") (pin "1") (pinfunction "1_1") (pintype "passive"))
      (node (ref "U4") (pin "7") (pinfunction "C_7") (pintype "passive"))
    )
    (net (code "57") (name "Net-(U4B-A)") (class "Default")
      (node (ref "R6") (pin "1") (pinfunction "1_1") (pintype "passive"))
      (node (ref "U4") (pin "4") (pinfunction "A_4") (pintype "passive"))
    )
    (net (code "58") (name "Net-(U6A-A)") (class "Default")
      (node (ref "R9_") (pin "1") (pinfunction "1_1") (pintype "passive"))
      (node (ref "U6") (pin "1") (pinfunction "A_1") (pintype "passive"))
    )
    (net (code "59") (name "Net-(U6B-A)") (class "Default")
      (node (ref "R9") (pin "1") (pinfunction "1_1") (pintype "passive"))
      (node (ref "U6") (pin "4") (pinfunction "A_4") (pintype "passive"))
    )
    (net (code "60") (name "unconnected-(J1-Pad3)") (class "Default")
      (node (ref "J1") (pin "3") (pinfunction "3_3") (pintype "passive"))
    )
    (net (code "61") (name "unconnected-(J1-Pad4)") (class "Default")
      (node (ref "J1") (pin "4") (pinfunction "4_4") (pintype "passive"))
    )
    (net (code "62") (name "unconnected-(J2-Pad3)") (class "Default")
      (node (ref "J2") (pin "3") (pinfunction "3_3") (pintype "passive"))
    )
    (net (code "63") (name "unconnected-(J2-Pad4)") (class "Default")
      (node (ref "J2") (pin "4") (pinfunction "4_4") (pintype "passive"))
    )
    (net (code "64") (name "unconnected-(RELE 24VDC-Pad2)") (class "Default")
      (node (ref "RELE 24VDC") (pin "2") (pinfunction "2_2") (pintype "passive"))
    )
    (net (code "65") (name "unconnected-(U2-RA5{slash}AN4{slash}~{SS}{slash}HLVDIN{slash}C2OUT-Pad7)") (class "Default")
      (node (ref "U2") (pin "7") (pinfunction "RA5/AN4/~{SS}/HLVDIN/C2OUT_7") (pintype "bidirectional"))
    )
    (net (code "66") (name "unconnected-(U2-RB0{slash}AN12{slash}INT0{slash}FLT0{slash}SDI{slash}SDA-Pad21)") (class "Default")
      (node (ref "U2") (pin "21") (pinfunction "RB0/AN12/INT0/FLT0/SDI/SDA_21") (pintype "bidirectional"))
    )
    (net (code "67") (name "unconnected-(U2-RB3{slash}AN9{slash}CCP2{slash}VPO-Pad24)") (class "Default")
      (node (ref "U2") (pin "24") (pinfunction "RB3/AN9/CCP2/VPO_24") (pintype "bidirectional"))
    )
    (net (code "68") (name "unconnected-(U2-RB4{slash}AN11{slash}KBI0-Pad25)") (class "Default")
      (node (ref "U2") (pin "25") (pinfunction "RB4/AN11/KBI0_25") (pintype "bidirectional"))
    )
    (net (code "69") (name "unconnected-(U2-RC4{slash}D-{slash}VM-Pad15)") (class "Default")
      (node (ref "U2") (pin "15") (pinfunction "RC4/D-/VM_15") (pintype "bidirectional"))
    )
    (net (code "70") (name "unconnected-(U2-RC5{slash}D+{slash}VP-Pad16)") (class "Default")
      (node (ref "U2") (pin "16") (pinfunction "RC5/D+/VP_16") (pintype "bidirectional"))
    )
    (net (code "71") (name "unconnected-(U2-VUSB-Pad14)") (class "Default")
      (node (ref "U2") (pin "14") (pinfunction "VUSB_14") (pintype "output"))
    )
  )
)
